# 002-H-01_SLS_to_CAN.net
KiCad netlist of a schematic drawn in Altium Designer
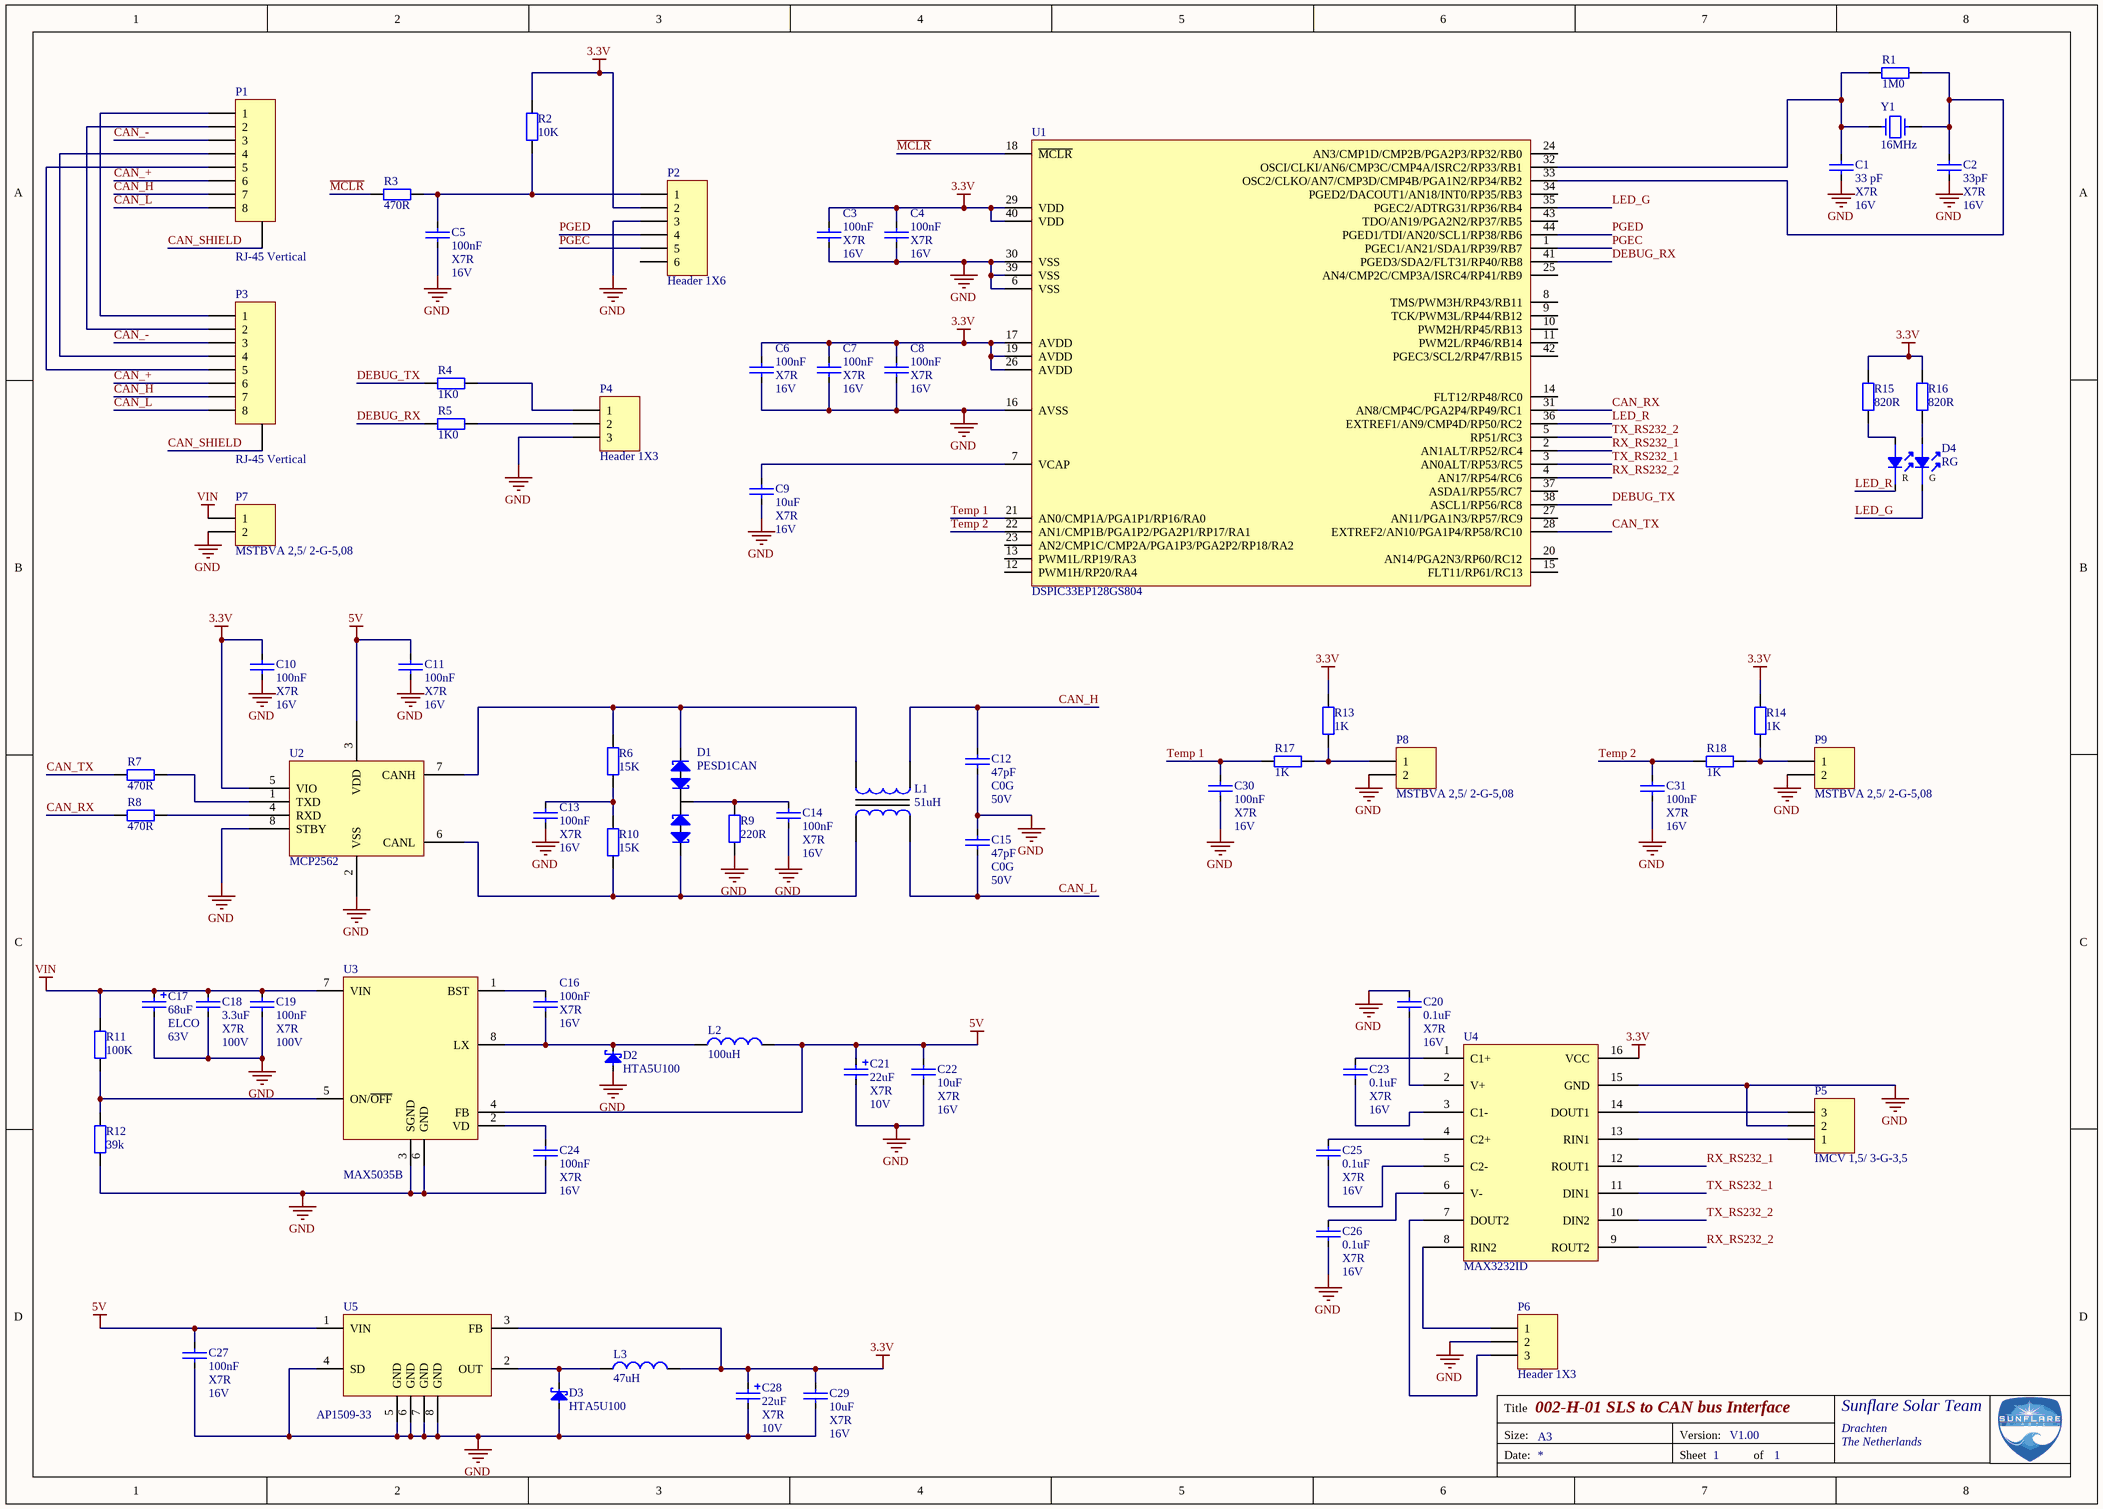
[diagram p0: 002-H-01 SLS to CAN.SchDoc]

(export (version "E")
  (design (tool "Eeschema 10.0.6"))
  (components
    (comp (ref "C1")
      (value "33 pF")
      (footprint "CAP0805")
      (description "Capacitor")
      (fields (field (name "DIELECTRIC") "X7R") (field (name "VOLTAGERATING") "16V"))
      (libsource (lib "002-H-01 SLS to CAN") (part "Capacitor"))
    )
    (comp (ref "C2")
      (value "33pF")
      (footprint "CAP0805")
      (description "Capacitor")
      (fields (field (name "DIELECTRIC") "X7R") (field (name "VOLTAGERATING") "16V"))
      (libsource (lib "002-H-01 SLS to CAN") (part "Capacitor"))
    )
    (comp (ref "C3")
      (value "100nF")
      (footprint "CAP0805")
      (description "Capacitor")
      (fields (field (name "DIELECTRIC") "X7R") (field (name "VOLTAGERATING") "16V"))
      (libsource (lib "002-H-01 SLS to CAN") (part "Capacitor"))
    )
    (comp (ref "C4")
      (value "100nF")
      (footprint "CAP0805")
      (description "Capacitor")
      (fields (field (name "DIELECTRIC") "X7R") (field (name "VOLTAGERATING") "16V"))
      (libsource (lib "002-H-01 SLS to CAN") (part "Capacitor"))
    )
    (comp (ref "C5")
      (value "100nF")
      (footprint "CAP0805")
      (description "Capacitor")
      (fields (field (name "DIELECTRIC") "X7R") (field (name "VOLTAGERATING") "16V"))
      (libsource (lib "002-H-01 SLS to CAN") (part "Capacitor"))
    )
    (comp (ref "C6")
      (value "100nF")
      (footprint "CAP0805")
      (description "Capacitor")
      (fields (field (name "DIELECTRIC") "X7R") (field (name "VOLTAGERATING") "16V"))
      (libsource (lib "002-H-01 SLS to CAN") (part "Capacitor"))
    )
    (comp (ref "C7")
      (value "100nF")
      (footprint "CAP0805")
      (description "Capacitor")
      (fields (field (name "DIELECTRIC") "X7R") (field (name "VOLTAGERATING") "16V"))
      (libsource (lib "002-H-01 SLS to CAN") (part "Capacitor"))
    )
    (comp (ref "C8")
      (value "100nF")
      (footprint "CAP0805")
      (description "Capacitor")
      (fields (field (name "DIELECTRIC") "X7R") (field (name "VOLTAGERATING") "16V"))
      (libsource (lib "002-H-01 SLS to CAN") (part "Capacitor"))
    )
    (comp (ref "C9")
      (value "10uF")
      (footprint "CAP1210")
      (description "Capacitor")
      (fields
        (field (name "MANUFACTURER") "TDK")
        (field (name "MANUFACTURER PART NO") "C3225X7R1C106K200AB")
        (field (name "DIELECTRIC") "X7R")
        (field (name "VOLTAGERATING") "16V")
      )
      (libsource (lib "002-H-01 SLS to CAN") (part "Capacitor"))
    )
    (comp (ref "C10")
      (value "100nF")
      (footprint "CAP0805")
      (description "Capacitor")
      (fields (field (name "DIELECTRIC") "X7R") (field (name "VOLTAGERATING") "16V"))
      (libsource (lib "002-H-01 SLS to CAN") (part "Capacitor"))
    )
    (comp (ref "C11")
      (value "100nF")
      (footprint "CAP0805")
      (description "Capacitor")
      (fields (field (name "DIELECTRIC") "X7R") (field (name "VOLTAGERATING") "16V"))
      (libsource (lib "002-H-01 SLS to CAN") (part "Capacitor"))
    )
    (comp (ref "C12")
      (value "47pF")
      (footprint "CAP0805")
      (description "Capacitor")
      (fields (field (name "DIELECTRIC") "C0G") (field (name "VOLTAGERATING") "50V"))
      (libsource (lib "002-H-01 SLS to CAN") (part "Capacitor"))
    )
    (comp (ref "C13")
      (value "100nF")
      (footprint "CAP0805")
      (description "Capacitor")
      (fields (field (name "DIELECTRIC") "X7R") (field (name "VOLTAGERATING") "16V"))
      (libsource (lib "002-H-01 SLS to CAN") (part "Capacitor"))
    )
    (comp (ref "C14")
      (value "100nF")
      (footprint "CAP0805")
      (description "Capacitor")
      (fields (field (name "DIELECTRIC") "X7R") (field (name "VOLTAGERATING") "16V"))
      (libsource (lib "002-H-01 SLS to CAN") (part "Capacitor"))
    )
    (comp (ref "C15")
      (value "47pF")
      (footprint "CAP0805")
      (description "Capacitor")
      (fields (field (name "DIELECTRIC") "C0G") (field (name "VOLTAGERATING") "50V"))
      (libsource (lib "002-H-01 SLS to CAN") (part "Capacitor"))
    )
    (comp (ref "C16")
      (value "100nF")
      (footprint "CAP0805")
      (description "Capacitor")
      (fields (field (name "DIELECTRIC") "X7R") (field (name "VOLTAGERATING") "16V"))
      (libsource (lib "002-H-01 SLS to CAN") (part "Capacitor"))
    )
    (comp (ref "C17")
      (value "68uF")
      (footprint "CAPP8383X62N")
      (description "Capacitor Pol")
      (fields
        (field (name "MANUFACTURER") "Panasonic")
        (field (name "MANUFACTURER PART NO") "EEEFK1J680UP")
        (field (name "DIELECTRIC") "ELCO")
        (field (name "VOLTAGERATING") "63V")
      )
      (libsource (lib "002-H-01 SLS to CAN") (part "CapacitorPol"))
    )
    (comp (ref "C18")
      (value "3.3uF")
      (footprint "CAP1210")
      (description "Capacitor")
      (fields
        (field (name "MANUFACTURER") "AVX")
        (field (name "MANUFACTURER PART NO") "12101C335KAZ2A")
        (field (name "DIELECTRIC") "X7R")
        (field (name "VOLTAGERATING") "100V")
      )
      (libsource (lib "002-H-01 SLS to CAN") (part "Capacitor"))
    )
    (comp (ref "C19")
      (value "100nF")
      (footprint "CAP0805")
      (description "Capacitor")
      (fields (field (name "DIELECTRIC") "X7R") (field (name "VOLTAGERATING") "100V"))
      (libsource (lib "002-H-01 SLS to CAN") (part "Capacitor"))
    )
    (comp (ref "C20")
      (value "0.1uF")
      (footprint "CAP0805")
      (description "Capacitor")
      (fields (field (name "DIELECTRIC") "X7R") (field (name "VOLTAGERATING") "16V"))
      (libsource (lib "002-H-01 SLS to CAN") (part "Capacitor"))
    )
    (comp (ref "C21")
      (value "22uF")
      (footprint "CAPAE4243X55M")
      (description "Capacitor Pol")
      (fields
        (field (name "MANUFACTURER") "PANASONIC")
        (field (name "MANUFACTURER PART NO") "EEEHA1A220WR")
        (field (name "DIELECTRIC") "X7R")
        (field (name "VOLTAGERATING") "10V")
      )
      (libsource (lib "002-H-01 SLS to CAN") (part "CapacitorPol"))
    )
    (comp (ref "C22")
      (value "10uF")
      (footprint "CAP1210")
      (description "Capacitor")
      (fields
        (field (name "MANUFACTURER") "TDK")
        (field (name "MANUFACTURER PART NO") "C3225X7R1C106K200AB")
        (field (name "DIELECTRIC") "X7R")
        (field (name "VOLTAGERATING") "16V")
      )
      (libsource (lib "002-H-01 SLS to CAN") (part "Capacitor"))
    )
    (comp (ref "C23")
      (value "0.1uF")
      (footprint "CAP0805")
      (description "Capacitor")
      (fields (field (name "DIELECTRIC") "X7R") (field (name "VOLTAGERATING") "16V"))
      (libsource (lib "002-H-01 SLS to CAN") (part "Capacitor"))
    )
    (comp (ref "C24")
      (value "100nF")
      (footprint "CAP0805")
      (description "Capacitor")
      (fields (field (name "DIELECTRIC") "X7R") (field (name "VOLTAGERATING") "16V"))
      (libsource (lib "002-H-01 SLS to CAN") (part "Capacitor"))
    )
    (comp (ref "C25")
      (value "0.1uF")
      (footprint "CAP0805")
      (description "Capacitor")
      (fields (field (name "DIELECTRIC") "X7R") (field (name "VOLTAGERATING") "16V"))
      (libsource (lib "002-H-01 SLS to CAN") (part "Capacitor"))
    )
    (comp (ref "C26")
      (value "0.1uF")
      (footprint "CAP0805")
      (description "Capacitor")
      (fields (field (name "DIELECTRIC") "X7R") (field (name "VOLTAGERATING") "16V"))
      (libsource (lib "002-H-01 SLS to CAN") (part "Capacitor"))
    )
    (comp (ref "C27")
      (value "100nF")
      (footprint "CAP0805")
      (description "Capacitor")
      (fields (field (name "DIELECTRIC") "X7R") (field (name "VOLTAGERATING") "16V"))
      (libsource (lib "002-H-01 SLS to CAN") (part "Capacitor"))
    )
    (comp (ref "C28")
      (value "22uF")
      (footprint "CAPAE4243X55M")
      (description "Capacitor Pol")
      (fields
        (field (name "MANUFACTURER") "PANASONIC")
        (field (name "MANUFACTURER PART NO") "EEEHA1A220WR")
        (field (name "DIELECTRIC") "X7R")
        (field (name "VOLTAGERATING") "10V")
      )
      (libsource (lib "002-H-01 SLS to CAN") (part "CapacitorPol"))
    )
    (comp (ref "C29")
      (value "10uF")
      (footprint "CAP1210")
      (description "Capacitor")
      (fields
        (field (name "MANUFACTURER") "TDK")
        (field (name "MANUFACTURER PART NO") "C3225X7R1C106K200AB")
        (field (name "DIELECTRIC") "X7R")
        (field (name "VOLTAGERATING") "16V")
      )
      (libsource (lib "002-H-01 SLS to CAN") (part "Capacitor"))
    )
    (comp (ref "C30")
      (value "100nF")
      (footprint "CAP0805")
      (description "Capacitor")
      (fields (field (name "DIELECTRIC") "X7R") (field (name "VOLTAGERATING") "16V"))
      (libsource (lib "002-H-01 SLS to CAN") (part "Capacitor"))
    )
    (comp (ref "C31")
      (value "100nF")
      (footprint "CAP0805")
      (description "Capacitor")
      (fields (field (name "DIELECTRIC") "X7R") (field (name "VOLTAGERATING") "16V"))
      (libsource (lib "002-H-01 SLS to CAN") (part "Capacitor"))
    )
    (comp (ref "D1")
      (value "PESD1CAN")
      (footprint "SOT23-3N")
      (description "ESD Protection Device, TVS, 70 V, SOT-23, 3 Pins")
      (fields (field (name "MANUFACTURER") "NXP"))
      (libsource (lib "002-H-01 SLS to CAN") (part "PESD1CAN"))
    )
    (comp (ref "D2")
      (value "HTA5U100")
      (footprint "DIODEDO-214AC")
      (description "Diode Schottky")
      (fields (field (name "MANUFACTURER") "Multicomp"))
      (libsource (lib "002-H-01 SLS to CAN") (part "Diode Schottky"))
    )
    (comp (ref "D3")
      (value "HTA5U100")
      (footprint "DIODEDO-214AC")
      (description "Diode Schottky")
      (fields (field (name "MANUFACTURER") "Multicomp"))
      (libsource (lib "002-H-01 SLS to CAN") (part "Diode Schottky"))
    )
    (comp (ref "D4")
      (value "RG")
      (footprint "CAC-75P125X160-4N")
      (description "Led RG")
      (fields
        (field (name "MANUFACTURER") "KINGBRIGHT")
        (field (name "MANUFACTURER PART NO") "KPTB-1612LVSURKCGKC")
      )
      (libsource (lib "002-H-01 SLS to CAN") (part "Led_RG"))
    )
    (comp (ref "L1")
      (value "51uH")
      (footprint "IND200P450X300-4N")
      (description "Choke common mode")
      (fields (field (name "MANUFACTURER") "Bourns") (field (name "MANUFACTURER PART NO") "SRF4532-510Y"))
      (libsource (lib "002-H-01 SLS to CAN") (part "Choke Common Mode"))
    )
    (comp (ref "L2")
      (value "100uH")
      (footprint "INDP3030X28N")
      (description "Inductor")
      (fields (field (name "MANUFACTURER") "BOURNS") (field (name "MANUFACTURER PART NO") "SDR0302-101KL"))
      (libsource (lib "002-H-01 SLS to CAN") (part "Inductor"))
    )
    (comp (ref "L3")
      (value "47uH")
      (footprint "INDP3030X28N")
      (description "Inductor")
      (fields (field (name "MANUFACTURER") "Bourns") (field (name "MANUFACTURER PART NO") "SDR0302-470KL"))
      (libsource (lib "002-H-01 SLS to CAN") (part "Inductor"))
    )
    (comp (ref "P1")
      (value "RJ-45 Vertical")
      (footprint "Amphenol RJ-45 Vertical")
      (description "RJ-45 VErtical")
      (fields (field (name "MANUFACTURER") "Amphenol") (field (name "MANUFACTURER PART NO") "RJHSE-3P80"))
      (libsource (lib "002-H-01 SLS to CAN") (part "RJ-45 Vertical"))
    )
    (comp (ref "P2")
      (value "Header 1X6")
      (footprint "Header1X6P100")
      (description "Connector 1X6")
      (libsource (lib "002-H-01 SLS to CAN") (part "Header1X6"))
    )
    (comp (ref "P3")
      (value "RJ-45 Vertical")
      (footprint "Amphenol RJ-45 Vertical")
      (description "RJ-45 VErtical")
      (fields (field (name "MANUFACTURER") "Amphenol") (field (name "MANUFACTURER PART NO") "RJHSE-3P80"))
      (libsource (lib "002-H-01 SLS to CAN") (part "RJ-45 Vertical"))
    )
    (comp (ref "P4")
      (value "Header 1X3")
      (footprint "Header1X3P100")
      (description "Connector 1X3")
      (libsource (lib "002-H-01 SLS to CAN") (part "Header1X3"))
    )
    (comp (ref "P5")
      (value "IMCV 1,5/ 3-G-3,5")
      (footprint "Phoenix IMCV 1,5/ 3-G-3,81")
      (description "IMCV 1,5/ 3-G-3,5 1830728")
      (libsource (lib "002-H-01 SLS to CAN") (part "Phoenix  IMCV 1,5/ 3-G-3,5"))
    )
    (comp (ref "P6")
      (value "Header 1X3")
      (footprint "Header1X3P100")
      (description "Connector 1X3")
      (libsource (lib "002-H-01 SLS to CAN") (part "Header1X3"))
    )
    (comp (ref "P7")
      (value "MSTBVA 2,5/ 2-G-5,08")
      (footprint "MSTBVA 2,5/ 2-G-5,08")
      (description "MSTBVA 2,5/ 2-G-5,08  1757242")
      (libsource (lib "002-H-01 SLS to CAN") (part "Phoenix  MSTBVA 2,5/ 2-G-5,08_1"))
    )
    (comp (ref "P8")
      (value "MSTBVA 2,5/ 2-G-5,08")
      (footprint "MSTBVA 2,5/ 2-G-5,08")
      (description "MSTBVA 2,5/ 2-G-5,08  1757242")
      (libsource (lib "002-H-01 SLS to CAN") (part "Phoenix  MSTBVA 2,5/ 2-G-5,08_1"))
    )
    (comp (ref "P9")
      (value "MSTBVA 2,5/ 2-G-5,08")
      (footprint "MSTBVA 2,5/ 2-G-5,08")
      (description "MSTBVA 2,5/ 2-G-5,08  1757242")
      (libsource (lib "002-H-01 SLS to CAN") (part "Phoenix  MSTBVA 2,5/ 2-G-5,08_1"))
    )
    (comp (ref "R1")
      (value "1M0")
      (footprint "RES0805")
      (description "Resistor")
      (fields (field (name "TOLERANCE") "1%"))
      (libsource (lib "002-H-01 SLS to CAN") (part "Resistor"))
    )
    (comp (ref "R2")
      (value "10K")
      (footprint "RES0805")
      (description "Resistor")
      (fields (field (name "TOLERANCE") "1%"))
      (libsource (lib "") (part "Resistor_1"))
    )
    (comp (ref "R3")
      (value "470R")
      (footprint "RES0805")
      (description "Resistor")
      (fields (field (name "TOLERANCE") "1%"))
      (libsource (lib "002-H-01 SLS to CAN") (part "Resistor"))
    )
    (comp (ref "R4")
      (value "1K0")
      (footprint "RES0805")
      (description "Resistor")
      (fields (field (name "TOLERANCE") "1%"))
      (libsource (lib "002-H-01 SLS to CAN") (part "Resistor"))
    )
    (comp (ref "R5")
      (value "1K0")
      (footprint "RES0805")
      (description "Resistor")
      (fields (field (name "TOLERANCE") "1%"))
      (libsource (lib "002-H-01 SLS to CAN") (part "Resistor"))
    )
    (comp (ref "R6")
      (value "15K")
      (footprint "RES0805")
      (description "Resistor")
      (fields (field (name "TOLERANCE") "1%"))
      (libsource (lib "") (part "Resistor_1"))
    )
    (comp (ref "R7")
      (value "470R")
      (footprint "RES0805")
      (description "Resistor")
      (fields (field (name "TOLERANCE") "1%"))
      (libsource (lib "002-H-01 SLS to CAN") (part "Resistor"))
    )
    (comp (ref "R8")
      (value "470R")
      (footprint "RES0805")
      (description "Resistor")
      (fields (field (name "TOLERANCE") "1%"))
      (libsource (lib "002-H-01 SLS to CAN") (part "Resistor"))
    )
    (comp (ref "R9")
      (value "220R")
      (footprint "RES0805")
      (description "Resistor")
      (fields (field (name "TOLERANCE") "1%"))
      (libsource (lib "") (part "Resistor_1"))
    )
    (comp (ref "R10")
      (value "15K")
      (footprint "RES0805")
      (description "Resistor")
      (fields (field (name "TOLERANCE") "1%"))
      (libsource (lib "") (part "Resistor_1"))
    )
    (comp (ref "R11")
      (value "100K")
      (footprint "RES0805")
      (description "Resistor")
      (fields (field (name "TOLERANCE") "1%"))
      (libsource (lib "") (part "Resistor_1"))
    )
    (comp (ref "R12")
      (value "39k")
      (footprint "RES0805")
      (description "Resistor")
      (fields (field (name "TOLERANCE") "1%"))
      (libsource (lib "") (part "Resistor_1"))
    )
    (comp (ref "R13")
      (value "1K")
      (footprint "RES0805")
      (description "Resistor")
      (fields (field (name "TOLERANCE") "1%"))
      (libsource (lib "") (part "Resistor_2"))
    )
    (comp (ref "R14")
      (value "1K")
      (footprint "RES0805")
      (description "Resistor")
      (fields (field (name "TOLERANCE") "1%"))
      (libsource (lib "") (part "Resistor_2"))
    )
    (comp (ref "R15")
      (value "820R")
      (footprint "RES0805")
      (description "Resistor")
      (fields (field (name "TOLERANCE") "1%"))
      (libsource (lib "") (part "Resistor_1"))
    )
    (comp (ref "R16")
      (value "820R")
      (footprint "RES0805")
      (description "Resistor")
      (fields (field (name "TOLERANCE") "1%"))
      (libsource (lib "") (part "Resistor_1"))
    )
    (comp (ref "R17")
      (value "1K")
      (footprint "RES0805")
      (description "Resistor")
      (fields (field (name "TOLERANCE") "1%"))
      (libsource (lib "002-H-01 SLS to CAN") (part "Resistor"))
    )
    (comp (ref "R18")
      (value "1K")
      (footprint "RES0805")
      (description "Resistor")
      (fields (field (name "TOLERANCE") "1%"))
      (libsource (lib "002-H-01 SLS to CAN") (part "Resistor"))
    )
    (comp (ref "U1")
      (value "DSPIC33EP128GS804")
      (footprint "TQFP80P1200X1200X120-44N")
      (fields
        (field (name "MANUFACTURER") "Microchip")
        (field (name "MANUFACTURER PART NO") "DSPIC33EP128GS804-I/PT")
      )
      (libsource (lib "002-H-01 SLS to CAN") (part "DSPIC33EP128GS804"))
    )
    (comp (ref "U2")
      (value "MCP2562")
      (footprint "SOIC-8N")
      (description "CAN Bus, Transceiver, CAN, LIN, 1, 1, 4.5 V, 5.5 V, SOIC")
      (fields (field (name "MANUFACTURER") "Microchip") (field (name "MANUFACTURER PART NO") "MCP2562-E/SN"))
      (libsource (lib "002-H-01 SLS to CAN") (part "MCP2562"))
    )
    (comp (ref "U3")
      (value "MAX5035B")
      (footprint "SOIC-8N")
      (description "5V 1A, 76V, High-Efficiency MAXPower Step-Down DC-DC Converter")
      (fields
        (field (name "MANUFACTURER") "Maxim Integrated Products")
        (field (name "MANUFACTURER PART NO") "MAX5035BUSA+T")
      )
      (libsource (lib "002-H-01 SLS to CAN") (part "MAX5035B"))
    )
    (comp (ref "U4")
      (value "MAX3232ID")
      (footprint "SOIC16_MAX3232")
      (description "RS232 tot TTL converter")
      (fields (field (name "MANUFACTURER") "TEXAS INSTRUMENTS"))
      (libsource (lib "002-H-01 SLS to CAN") (part "MAX3232"))
    )
    (comp (ref "U5")
      (value "AP1509-33")
      (footprint "SOIC-8N")
      (description "150KHz, 2A PWM BUCK DC/DC CONVERTER")
      (fields
        (field (name "MANUFACTURER") "Diodes Inc")
        (field (name "MANUFACTURER PART NO") "AP1509-33SG-13")
      )
      (libsource (lib "002-H-01 SLS to CAN") (part "AP1509-33"))
    )
    (comp (ref "Y1")
      (value "16MHz")
      (footprint "XT49M-2016M")
      (description "Crystal")
      (fields
        (field (name "MANUFACTURER") "Multicomp")
        (field (name "MANUFACTURER PART NO") "MCRSD16000F183000RR")
      )
      (libsource (lib "002-H-01 SLS to CAN") (part "Crystal"))
    )
  )
  (nets
    (net (code "1") (name "/CAN_+") (class "Default")
      (node (ref "P1") (pin "6") (pinfunction "6_6") (pintype "passive"))
      (node (ref "P3") (pin "6") (pinfunction "6_6") (pintype "passive"))
    )
    (net (code "2") (name "/CAN_-") (class "Default")
      (node (ref "P1") (pin "3") (pinfunction "3_3") (pintype "passive"))
      (node (ref "P3") (pin "3") (pinfunction "3_3") (pintype "passive"))
    )
    (net (code "3") (name "/CAN_H") (class "Default")
      (node (ref "C12") (pin "2") (pinfunction "2_2") (pintype "passive"))
      (node (ref "L1") (pin "3") (pinfunction "3_3") (pintype "passive"))
      (node (ref "P1") (pin "7") (pinfunction "7_7") (pintype "passive"))
      (node (ref "P3") (pin "7") (pinfunction "7_7") (pintype "passive"))
    )
    (net (code "4") (name "/CAN_L") (class "Default")
      (node (ref "C15") (pin "1") (pinfunction "1_1") (pintype "passive"))
      (node (ref "L1") (pin "2") (pinfunction "2_2") (pintype "passive"))
      (node (ref "P1") (pin "8") (pinfunction "8_8") (pintype "passive"))
      (node (ref "P3") (pin "8") (pinfunction "8_8") (pintype "passive"))
    )
    (net (code "5") (name "/CAN_RX") (class "Default")
      (node (ref "R8") (pin "1") (pinfunction "1_1") (pintype "passive"))
      (node (ref "U1") (pin "31") (pinfunction "AN8/CMP4C/PGA2P4/RP49/RC1_31") (pintype "passive"))
    )
    (net (code "6") (name "/CAN_SHIELD") (class "Default")
      (node (ref "P1") (pin "9") (pinfunction "G_9") (pintype "passive"))
      (node (ref "P3") (pin "9") (pinfunction "G_9") (pintype "passive"))
    )
    (net (code "7") (name "/CAN_TX") (class "Default")
      (node (ref "R7") (pin "1") (pinfunction "1_1") (pintype "passive"))
      (node (ref "U1") (pin "28") (pinfunction "EXTREF2/AN10/PGA1P4/RP58/RC10_28") (pintype "passive"))
    )
    (net (code "8") (name "/DEBUG_RX") (class "Default")
      (node (ref "R5") (pin "1") (pinfunction "1_1") (pintype "passive"))
      (node (ref "U1") (pin "41") (pinfunction "PGED3/SDA2/FLT31/RP40/RB8_41") (pintype "passive"))
    )
    (net (code "9") (name "/DEBUG_TX") (class "Default")
      (node (ref "R4") (pin "1") (pinfunction "1_1") (pintype "passive"))
      (node (ref "U1") (pin "38") (pinfunction "ASCL1/RP56/RC8_38") (pintype "passive"))
    )
    (net (code "10") (name "/LED_G") (class "Default")
      (node (ref "D4") (pin "4") (pinfunction "K_G_4") (pintype "passive"))
      (node (ref "U1") (pin "35") (pinfunction "PGEC2/ADTRG31/RP36/RB4_35") (pintype "passive"))
    )
    (net (code "11") (name "/LED_R") (class "Default")
      (node (ref "D4") (pin "2") (pinfunction "K_R_2") (pintype "passive"))
      (node (ref "U1") (pin "36") (pinfunction "EXTREF1/AN9/CMP4D/RP50/RC2_36") (pintype "passive"))
    )
    (net (code "12") (name "/PGEC") (class "Default")
      (node (ref "P2") (pin "5") (pinfunction "5_5") (pintype "passive"))
      (node (ref "U1") (pin "1") (pinfunction "PGEC1/AN21/SDA1/RP39/RB7_1") (pintype "passive"))
    )
    (net (code "13") (name "/PGED") (class "Default")
      (node (ref "P2") (pin "4") (pinfunction "4_4") (pintype "passive"))
      (node (ref "U1") (pin "44") (pinfunction "PGED1/TDI/AN20/SCL1/RP38/RB6_44") (pintype "passive"))
    )
    (net (code "14") (name "/RX_RS232_1") (class "Default")
      (node (ref "U1") (pin "2") (pinfunction "AN1ALT/RP52/RC4_2") (pintype "passive"))
      (node (ref "U4") (pin "12") (pinfunction "ROUT1_12") (pintype "passive"))
    )
    (net (code "15") (name "/RX_RS232_2") (class "Default")
      (node (ref "U1") (pin "4") (pinfunction "AN17/RP54/RC6_4") (pintype "passive"))
      (node (ref "U4") (pin "9") (pinfunction "ROUT2_9") (pintype "passive"))
    )
    (net (code "16") (name "/TX_RS232_1") (class "Default")
      (node (ref "U1") (pin "3") (pinfunction "AN0ALT/RP53/RC5_3") (pintype "passive"))
      (node (ref "U4") (pin "11") (pinfunction "DIN1_11") (pintype "passive"))
    )
    (net (code "17") (name "/TX_RS232_2") (class "Default")
      (node (ref "U1") (pin "5") (pinfunction "RP51/RC3_5") (pintype "passive"))
      (node (ref "U4") (pin "10") (pinfunction "DIN2_10") (pintype "passive"))
    )
    (net (code "18") (name "/Temp 1") (class "Default")
      (node (ref "C30") (pin "2") (pinfunction "2_2") (pintype "passive"))
      (node (ref "R17") (pin "1") (pinfunction "1_1") (pintype "passive"))
      (node (ref "U1") (pin "21") (pinfunction "AN0/CMP1A/PGA1P1/RP16/RA0_21") (pintype "passive"))
    )
    (net (code "19") (name "/Temp 2") (class "Default")
      (node (ref "C31") (pin "2") (pinfunction "2_2") (pintype "passive"))
      (node (ref "R18") (pin "1") (pinfunction "1_1") (pintype "passive"))
      (node (ref "U1") (pin "22") (pinfunction "AN1/CMP1B/PGA1P2/PGA2P1/RP17/RA1_22") (pintype "passive"))
    )
    (net (code "20") (name "/~{MCLR}") (class "Default")
      (node (ref "R3") (pin "1") (pinfunction "1_1") (pintype "passive"))
      (node (ref "U1") (pin "18") (pinfunction "~{MCLR}_18") (pintype "passive"))
    )
    (net (code "21") (name "3.3V") (class "Default")
      (node (ref "C10") (pin "2") (pinfunction "2_2") (pintype "passive"))
      (node (ref "C28") (pin "1") (pinfunction "1_1") (pintype "passive"))
      (node (ref "C29") (pin "2") (pinfunction "2_2") (pintype "passive"))
      (node (ref "C3") (pin "2") (pinfunction "2_2") (pintype "passive"))
      (node (ref "C4") (pin "2") (pinfunction "2_2") (pintype "passive"))
      (node (ref "C6") (pin "2") (pinfunction "2_2") (pintype "passive"))
      (node (ref "C7") (pin "2") (pinfunction "2_2") (pintype "passive"))
      (node (ref "C8") (pin "2") (pinfunction "2_2") (pintype "passive"))
      (node (ref "L3") (pin "2") (pinfunction "2_2") (pintype "passive"))
      (node (ref "P2") (pin "2") (pinfunction "2_2") (pintype "passive"))
      (node (ref "R13") (pin "2") (pinfunction "2_2") (pintype "passive"))
      (node (ref "R14") (pin "2") (pinfunction "2_2") (pintype "passive"))
      (node (ref "R15") (pin "1") (pinfunction "1_1") (pintype "passive"))
      (node (ref "R16") (pin "1") (pinfunction "1_1") (pintype "passive"))
      (node (ref "R2") (pin "1") (pinfunction "1_1") (pintype "passive"))
      (node (ref "U1") (pin "17") (pinfunction "AVDD_17") (pintype "passive"))
      (node (ref "U1") (pin "19") (pinfunction "AVDD_19") (pintype "passive"))
      (node (ref "U1") (pin "26") (pinfunction "AVDD_26") (pintype "passive"))
      (node (ref "U1") (pin "29") (pinfunction "VDD_29") (pintype "passive"))
      (node (ref "U1") (pin "40") (pinfunction "VDD_40") (pintype "passive"))
      (node (ref "U2") (pin "5") (pinfunction "VIO_5") (pintype "passive"))
      (node (ref "U4") (pin "16") (pinfunction "VCC_16") (pintype "passive"))
      (node (ref "U5") (pin "3") (pinfunction "FB_3") (pintype "passive"))
    )
    (net (code "22") (name "5V") (class "Default")
      (node (ref "C11") (pin "2") (pinfunction "2_2") (pintype "passive"))
      (node (ref "C21") (pin "1") (pinfunction "1_1") (pintype "passive"))
      (node (ref "C22") (pin "2") (pinfunction "2_2") (pintype "passive"))
      (node (ref "C27") (pin "2") (pinfunction "2_2") (pintype "passive"))
      (node (ref "L2") (pin "2") (pinfunction "2_2") (pintype "passive"))
      (node (ref "U2") (pin "3") (pinfunction "VDD_3") (pintype "passive"))
      (node (ref "U3") (pin "4") (pinfunction "FB_4") (pintype "passive"))
      (node (ref "U5") (pin "1") (pinfunction "VIN_1") (pintype "passive"))
    )
    (net (code "23") (name "GND") (class "Default")
      (node (ref "C1") (pin "1") (pinfunction "1_1") (pintype "passive"))
      (node (ref "C10") (pin "1") (pinfunction "1_1") (pintype "passive"))
      (node (ref "C11") (pin "1") (pinfunction "1_1") (pintype "passive"))
      (node (ref "C12") (pin "1") (pinfunction "1_1") (pintype "passive"))
      (node (ref "C13") (pin "1") (pinfunction "1_1") (pintype "passive"))
      (node (ref "C14") (pin "1") (pinfunction "1_1") (pintype "passive"))
      (node (ref "C15") (pin "2") (pinfunction "2_2") (pintype "passive"))
      (node (ref "C17") (pin "2") (pinfunction "2_2") (pintype "passive"))
      (node (ref "C18") (pin "1") (pinfunction "1_1") (pintype "passive"))
      (node (ref "C19") (pin "1") (pinfunction "1_1") (pintype "passive"))
      (node (ref "C2") (pin "1") (pinfunction "1_1") (pintype "passive"))
      (node (ref "C20") (pin "2") (pinfunction "2_2") (pintype "passive"))
      (node (ref "C21") (pin "2") (pinfunction "2_2") (pintype "passive"))
      (node (ref "C22") (pin "1") (pinfunction "1_1") (pintype "passive"))
      (node (ref "C24") (pin "1") (pinfunction "1_1") (pintype "passive"))
      (node (ref "C26") (pin "1") (pinfunction "1_1") (pintype "passive"))
      (node (ref "C27") (pin "1") (pinfunction "1_1") (pintype "passive"))
      (node (ref "C28") (pin "2") (pinfunction "2_2") (pintype "passive"))
      (node (ref "C29") (pin "1") (pinfunction "1_1") (pintype "passive"))
      (node (ref "C3") (pin "1") (pinfunction "1_1") (pintype "passive"))
      (node (ref "C30") (pin "1") (pinfunction "1_1") (pintype "passive"))
      (node (ref "C31") (pin "1") (pinfunction "1_1") (pintype "passive"))
      (node (ref "C4") (pin "1") (pinfunction "1_1") (pintype "passive"))
      (node (ref "C5") (pin "2") (pinfunction "2_2") (pintype "passive"))
      (node (ref "C6") (pin "1") (pinfunction "1_1") (pintype "passive"))
      (node (ref "C7") (pin "1") (pinfunction "1_1") (pintype "passive"))
      (node (ref "C8") (pin "1") (pinfunction "1_1") (pintype "passive"))
      (node (ref "C9") (pin "1") (pinfunction "1_1") (pintype "passive"))
      (node (ref "D2") (pin "2") (pinfunction "A_2") (pintype "passive"))
      (node (ref "D3") (pin "2") (pinfunction "A_2") (pintype "passive"))
      (node (ref "P2") (pin "3") (pinfunction "3_3") (pintype "passive"))
      (node (ref "P4") (pin "3") (pinfunction "3_3") (pintype "passive"))
      (node (ref "P5") (pin "2") (pinfunction "2_2") (pintype "passive"))
      (node (ref "P6") (pin "2") (pinfunction "2_2") (pintype "passive"))
      (node (ref "P7") (pin "2") (pinfunction "2_2") (pintype "passive"))
      (node (ref "P8") (pin "2") (pinfunction "2_2") (pintype "passive"))
      (node (ref "P9") (pin "2") (pinfunction "2_2") (pintype "passive"))
      (node (ref "R12") (pin "2") (pinfunction "2_2") (pintype "passive"))
      (node (ref "R9") (pin "2") (pinfunction "2_2") (pintype "passive"))
      (node (ref "U1") (pin "16") (pinfunction "AVSS_16") (pintype "passive"))
      (node (ref "U1") (pin "30") (pinfunction "VSS_30") (pintype "passive"))
      (node (ref "U1") (pin "39") (pinfunction "VSS_39") (pintype "passive"))
      (node (ref "U1") (pin "6") (pinfunction "VSS_6") (pintype "passive"))
      (node (ref "U2") (pin "2") (pinfunction "VSS_2") (pintype "passive"))
      (node (ref "U2") (pin "8") (pinfunction "STBY_8") (pintype "passive"))
      (node (ref "U3") (pin "3") (pinfunction "SGND_3") (pintype "passive"))
      (node (ref "U3") (pin "6") (pinfunction "GND_6") (pintype "passive"))
      (node (ref "U4") (pin "15") (pinfunction "GND_15") (pintype "passive"))
      (node (ref "U5") (pin "4") (pinfunction "SD_4") (pintype "passive"))
      (node (ref "U5") (pin "5") (pinfunction "GND_5") (pintype "passive"))
      (node (ref "U5") (pin "6") (pinfunction "GND_6") (pintype "passive"))
      (node (ref "U5") (pin "7") (pinfunction "GND_7") (pintype "passive"))
      (node (ref "U5") (pin "8") (pinfunction "GND_8") (pintype "passive"))
    )
    (net (code "24") (name "Net-(C5-Pad1)") (class "Default")
      (node (ref "C5") (pin "1") (pinfunction "1_1") (pintype "passive"))
      (node (ref "P2") (pin "1") (pinfunction "1_1") (pintype "passive"))
      (node (ref "R2") (pin "2") (pinfunction "2_2") (pintype "passive"))
      (node (ref "R3") (pin "2") (pinfunction "2_2") (pintype "passive"))
    )
    (net (code "25") (name "Net-(C13-Pad2)") (class "Default")
      (node (ref "C13") (pin "2") (pinfunction "2_2") (pintype "passive"))
      (node (ref "R10") (pin "1") (pinfunction "1_1") (pintype "passive"))
      (node (ref "R6") (pin "2") (pinfunction "2_2") (pintype "passive"))
    )
    (net (code "26") (name "Net-(C14-Pad2)") (class "Default")
      (node (ref "C14") (pin "2") (pinfunction "2_2") (pintype "passive"))
      (node (ref "D1") (pin "3") (pinfunction "3_3") (pintype "passive"))
      (node (ref "R9") (pin "1") (pinfunction "1_1") (pintype "passive"))
    )
    (net (code "27") (name "Net-(D2-K)") (class "Default")
      (node (ref "C16") (pin "1") (pinfunction "1_1") (pintype "passive"))
      (node (ref "D2") (pin "1") (pinfunction "K_1") (pintype "passive"))
      (node (ref "L2") (pin "1") (pinfunction "1_1") (pintype "passive"))
      (node (ref "U3") (pin "8") (pinfunction "LX_8") (pintype "passive"))
    )
    (net (code "28") (name "Net-(D3-K)") (class "Default")
      (node (ref "D3") (pin "1") (pinfunction "K_1") (pintype "passive"))
      (node (ref "L3") (pin "1") (pinfunction "1_1") (pintype "passive"))
      (node (ref "U5") (pin "2") (pinfunction "OUT_2") (pintype "passive"))
    )
    (net (code "29") (name "Net-(D4-A_G)") (class "Default")
      (node (ref "D4") (pin "3") (pinfunction "A_G_3") (pintype "passive"))
      (node (ref "R16") (pin "2") (pinfunction "2_2") (pintype "passive"))
    )
    (net (code "30") (name "Net-(D4-A_R)") (class "Default")
      (node (ref "D4") (pin "1") (pinfunction "A_R_1") (pintype "passive"))
      (node (ref "R15") (pin "2") (pinfunction "2_2") (pintype "passive"))
    )
    (net (code "31") (name "Net-(P1-Pad1)") (class "Default")
      (node (ref "P1") (pin "1") (pinfunction "1_1") (pintype "passive"))
      (node (ref "P3") (pin "1") (pinfunction "1_1") (pintype "passive"))
    )
    (net (code "32") (name "Net-(P1-Pad2)") (class "Default")
      (node (ref "P1") (pin "2") (pinfunction "2_2") (pintype "passive"))
      (node (ref "P3") (pin "2") (pinfunction "2_2") (pintype "passive"))
    )
    (net (code "33") (name "Net-(P1-Pad4)") (class "Default")
      (node (ref "P1") (pin "4") (pinfunction "4_4") (pintype "passive"))
      (node (ref "P3") (pin "4") (pinfunction "4_4") (pintype "passive"))
    )
    (net (code "34") (name "Net-(P1-Pad5)") (class "Default")
      (node (ref "P1") (pin "5") (pinfunction "5_5") (pintype "passive"))
      (node (ref "P3") (pin "5") (pinfunction "5_5") (pintype "passive"))
    )
    (net (code "35") (name "Net-(P4-Pad1)") (class "Default")
      (node (ref "P4") (pin "1") (pinfunction "1_1") (pintype "passive"))
      (node (ref "R4") (pin "2") (pinfunction "2_2") (pintype "passive"))
    )
    (net (code "36") (name "Net-(P4-Pad2)") (class "Default")
      (node (ref "P4") (pin "2") (pinfunction "2_2") (pintype "passive"))
      (node (ref "R5") (pin "2") (pinfunction "2_2") (pintype "passive"))
    )
    (net (code "37") (name "Net-(P8-Pad1)") (class "Default")
      (node (ref "P8") (pin "1") (pinfunction "1_1") (pintype "passive"))
      (node (ref "R13") (pin "1") (pinfunction "1_1") (pintype "passive"))
      (node (ref "R17") (pin "2") (pinfunction "2_2") (pintype "passive"))
    )
    (net (code "38") (name "Net-(P9-Pad1)") (class "Default")
      (node (ref "P9") (pin "1") (pinfunction "1_1") (pintype "passive"))
      (node (ref "R14") (pin "1") (pinfunction "1_1") (pintype "passive"))
      (node (ref "R18") (pin "2") (pinfunction "2_2") (pintype "passive"))
    )
    (net (code "39") (name "Net-(U1-OSC2{slash}CLKO{slash}AN7{slash}CMP3D{slash}CMP4B{slash}PGA1N2{slash}RP34{slash}RB2)") (class "Default")
      (node (ref "C2") (pin "2") (pinfunction "2_2") (pintype "passive"))
      (node (ref "R1") (pin "2") (pinfunction "2_2") (pintype "passive"))
      (node (ref "U1") (pin "33") (pinfunction "OSC2/CLKO/AN7/CMP3D/CMP4B/PGA1N2/RP34/RB2_33") (pintype "passive"))
      (node (ref "Y1") (pin "2") (pinfunction "2_2") (pintype "passive"))
    )
    (net (code "40") (name "Net-(U1-OSCI{slash}CLKI{slash}AN6{slash}CMP3C{slash}CMP4A{slash}ISRC2{slash}RP33{slash}RB1)") (class "Default")
      (node (ref "C1") (pin "2") (pinfunction "2_2") (pintype "passive"))
      (node (ref "R1") (pin "1") (pinfunction "1_1") (pintype "passive"))
      (node (ref "U1") (pin "32") (pinfunction "OSCI/CLKI/AN6/CMP3C/CMP4A/ISRC2/RP33/RB1_32") (pintype "passive"))
      (node (ref "Y1") (pin "1") (pinfunction "1_1") (pintype "passive"))
    )
    (net (code "41") (name "Net-(U1-VCAP)") (class "Default")
      (node (ref "C9") (pin "2") (pinfunction "2_2") (pintype "passive"))
      (node (ref "U1") (pin "7") (pinfunction "VCAP_7") (pintype "passive"))
    )
    (net (code "42") (name "Net-(U2-CANH)") (class "Default")
      (node (ref "D1") (pin "1") (pinfunction "1_1") (pintype "passive"))
      (node (ref "L1") (pin "4") (pinfunction "4_4") (pintype "passive"))
      (node (ref "R6") (pin "1") (pinfunction "1_1") (pintype "passive"))
      (node (ref "U2") (pin "7") (pinfunction "CANH_7") (pintype "passive"))
    )
    (net (code "43") (name "Net-(U2-CANL)") (class "Default")
      (node (ref "D1") (pin "2") (pinfunction "2_2") (pintype "passive"))
      (node (ref "L1") (pin "1") (pinfunction "1_1") (pintype "passive"))
      (node (ref "R10") (pin "2") (pinfunction "2_2") (pintype "passive"))
      (node (ref "U2") (pin "6") (pinfunction "CANL_6") (pintype "passive"))
    )
    (net (code "44") (name "Net-(U2-RXD)") (class "Default")
      (node (ref "R8") (pin "2") (pinfunction "2_2") (pintype "passive"))
      (node (ref "U2") (pin "4") (pinfunction "RXD_4") (pintype "passive"))
    )
    (net (code "45") (name "Net-(U2-TXD)") (class "Default")
      (node (ref "R7") (pin "2") (pinfunction "2_2") (pintype "passive"))
      (node (ref "U2") (pin "1") (pinfunction "TXD_1") (pintype "passive"))
    )
    (net (code "46") (name "Net-(U3-BST)") (class "Default")
      (node (ref "C16") (pin "2") (pinfunction "2_2") (pintype "passive"))
      (node (ref "U3") (pin "1") (pinfunction "BST_1") (pintype "passive"))
    )
    (net (code "47") (name "Net-(U3-ON{slash}~{OFF})") (class "Default")
      (node (ref "R11") (pin "2") (pinfunction "2_2") (pintype "passive"))
      (node (ref "R12") (pin "1") (pinfunction "1_1") (pintype "passive"))
      (node (ref "U3") (pin "5") (pinfunction "ON/~{OFF}_5") (pintype "passive"))
    )
    (net (code "48") (name "Net-(U3-VD)") (class "Default")
      (node (ref "C24") (pin "2") (pinfunction "2_2") (pintype "passive"))
      (node (ref "U3") (pin "2") (pinfunction "VD_2") (pintype "passive"))
    )
    (net (code "49") (name "Net-(U4-C1+)") (class "Default")
      (node (ref "C23") (pin "2") (pinfunction "2_2") (pintype "passive"))
      (node (ref "U4") (pin "1") (pinfunction "C1+_1") (pintype "passive"))
    )
    (net (code "50") (name "Net-(U4-C1-)") (class "Default")
      (node (ref "C23") (pin "1") (pinfunction "1_1") (pintype "passive"))
      (node (ref "U4") (pin "3") (pinfunction "C1-_3") (pintype "passive"))
    )
    (net (code "51") (name "Net-(U4-C2+)") (class "Default")
      (node (ref "C25") (pin "2") (pinfunction "2_2") (pintype "passive"))
      (node (ref "U4") (pin "4") (pinfunction "C2+_4") (pintype "passive"))
    )
    (net (code "52") (name "Net-(U4-C2-)") (class "Default")
      (node (ref "C25") (pin "1") (pinfunction "1_1") (pintype "passive"))
      (node (ref "U4") (pin "5") (pinfunction "C2-_5") (pintype "passive"))
    )
    (net (code "53") (name "Net-(U4-DOUT1)") (class "Default")
      (node (ref "P5") (pin "3") (pinfunction "3_3") (pintype "passive"))
      (node (ref "U4") (pin "14") (pinfunction "DOUT1_14") (pintype "passive"))
    )
    (net (code "54") (name "Net-(U4-DOUT2)") (class "Default")
      (node (ref "P6") (pin "3") (pinfunction "3_3") (pintype "passive"))
      (node (ref "U4") (pin "7") (pinfunction "DOUT2_7") (pintype "passive"))
    )
    (net (code "55") (name "Net-(U4-RIN1)") (class "Default")
      (node (ref "P5") (pin "1") (pinfunction "1_1") (pintype "passive"))
      (node (ref "U4") (pin "13") (pinfunction "RIN1_13") (pintype "passive"))
    )
    (net (code "56") (name "Net-(U4-RIN2)") (class "Default")
      (node (ref "P6") (pin "1") (pinfunction "1_1") (pintype "passive"))
      (node (ref "U4") (pin "8") (pinfunction "RIN2_8") (pintype "passive"))
    )
    (net (code "57") (name "Net-(U4-V+)") (class "Default")
      (node (ref "C20") (pin "1") (pinfunction "1_1") (pintype "passive"))
      (node (ref "U4") (pin "2") (pinfunction "V+_2") (pintype "passive"))
    )
    (net (code "58") (name "Net-(U4-V-)") (class "Default")
      (node (ref "C26") (pin "2") (pinfunction "2_2") (pintype "passive"))
      (node (ref "U4") (pin "6") (pinfunction "V-_6") (pintype "passive"))
    )
    (net (code "59") (name "VIN") (class "Default")
      (node (ref "C17") (pin "1") (pinfunction "1_1") (pintype "passive"))
      (node (ref "C18") (pin "2") (pinfunction "2_2") (pintype "passive"))
      (node (ref "C19") (pin "2") (pinfunction "2_2") (pintype "passive"))
      (node (ref "P7") (pin "1") (pinfunction "1_1") (pintype "passive"))
      (node (ref "R11") (pin "1") (pinfunction "1_1") (pintype "passive"))
      (node (ref "U3") (pin "7") (pinfunction "VIN_7") (pintype "passive"))
    )
    (net (code "60") (name "unconnected-(P2-Pad6)") (class "Default")
      (node (ref "P2") (pin "6") (pinfunction "6_6") (pintype "passive"))
    )
    (net (code "61") (name "unconnected-(U1-AN2{slash}CMP1C{slash}CMP2A{slash}PGA1P3{slash}PGA2P2{slash}RP18{slash}RA2-Pad23)") (class "Default")
      (node (ref "U1") (pin "23") (pinfunction "AN2/CMP1C/CMP2A/PGA1P3/PGA2P2/RP18/RA2_23") (pintype "passive"))
    )
    (net (code "62") (name "unconnected-(U1-AN3{slash}CMP1D{slash}CMP2B{slash}PGA2P3{slash}RP32{slash}RB0-Pad24)") (class "Default")
      (node (ref "U1") (pin "24") (pinfunction "AN3/CMP1D/CMP2B/PGA2P3/RP32/RB0_24") (pintype "passive"))
    )
    (net (code "63") (name "unconnected-(U1-AN4{slash}CMP2C{slash}CMP3A{slash}ISRC4{slash}RP41{slash}RB9-Pad25)") (class "Default")
      (node (ref "U1") (pin "25") (pinfunction "AN4/CMP2C/CMP3A/ISRC4/RP41/RB9_25") (pintype "passive"))
    )
    (net (code "64") (name "unconnected-(U1-AN11{slash}PGA1N3{slash}RP57{slash}RC9-Pad27)") (class "Default")
      (node (ref "U1") (pin "27") (pinfunction "AN11/PGA1N3/RP57/RC9_27") (pintype "passive"))
    )
    (net (code "65") (name "unconnected-(U1-AN14{slash}PGA2N3{slash}RP60{slash}RC12-Pad20)") (class "Default")
      (node (ref "U1") (pin "20") (pinfunction "AN14/PGA2N3/RP60/RC12_20") (pintype "passive"))
    )
    (net (code "66") (name "unconnected-(U1-ASDA1{slash}RP55{slash}RC7-Pad37)") (class "Default")
      (node (ref "U1") (pin "37") (pinfunction "ASDA1/RP55/RC7_37") (pintype "passive"))
    )
    (net (code "67") (name "unconnected-(U1-FLT11{slash}RP61{slash}RC13-Pad15)") (class "Default")
      (node (ref "U1") (pin "15") (pinfunction "FLT11/RP61/RC13_15") (pintype "passive"))
    )
    (net (code "68") (name "unconnected-(U1-FLT12{slash}RP48{slash}RC0-Pad14)") (class "Default")
      (node (ref "U1") (pin "14") (pinfunction "FLT12/RP48/RC0_14") (pintype "passive"))
    )
    (net (code "69") (name "unconnected-(U1-PGEC3{slash}SCL2{slash}RP47{slash}RB15-Pad42)") (class "Default")
      (node (ref "U1") (pin "42") (pinfunction "PGEC3/SCL2/RP47/RB15_42") (pintype "passive"))
    )
    (net (code "70") (name "unconnected-(U1-PGED2{slash}DACOUT1{slash}AN18{slash}INT0{slash}RP35{slash}RB3-Pad34)") (class "Default")
      (node (ref "U1") (pin "34") (pinfunction "PGED2/DACOUT1/AN18/INT0/RP35/RB3_34") (pintype "passive"))
    )
    (net (code "71") (name "unconnected-(U1-PWM1H{slash}RP20{slash}RA4-Pad12)") (class "Default")
      (node (ref "U1") (pin "12") (pinfunction "PWM1H/RP20/RA4_12") (pintype "passive"))
    )
    (net (code "72") (name "unconnected-(U1-PWM1L{slash}RP19{slash}RA3-Pad13)") (class "Default")
      (node (ref "U1") (pin "13") (pinfunction "PWM1L/RP19/RA3_13") (pintype "passive"))
    )
    (net (code "73") (name "unconnected-(U1-PWM2H{slash}RP45{slash}RB13-Pad10)") (class "Default")
      (node (ref "U1") (pin "10") (pinfunction "PWM2H/RP45/RB13_10") (pintype "passive"))
    )
    (net (code "74") (name "unconnected-(U1-PWM2L{slash}RP46{slash}RB14-Pad11)") (class "Default")
      (node (ref "U1") (pin "11") (pinfunction "PWM2L/RP46/RB14_11") (pintype "passive"))
    )
    (net (code "75") (name "unconnected-(U1-TCK{slash}PWM3L{slash}RP44{slash}RB12-Pad9)") (class "Default")
      (node (ref "U1") (pin "9") (pinfunction "TCK/PWM3L/RP44/RB12_9") (pintype "passive"))
    )
    (net (code "76") (name "unconnected-(U1-TDO{slash}AN19{slash}PGA2N2{slash}RP37{slash}RB5-Pad43)") (class "Default")
      (node (ref "U1") (pin "43") (pinfunction "TDO/AN19/PGA2N2/RP37/RB5_43") (pintype "passive"))
    )
    (net (code "77") (name "unconnected-(U1-TMS{slash}PWM3H{slash}RP43{slash}RB11-Pad8)") (class "Default")
      (node (ref "U1") (pin "8") (pinfunction "TMS/PWM3H/RP43/RB11_8") (pintype "passive"))
    )
  )
)
